# reduktor_light.net
KiCad netlist of a schematic drawn in EAGLE
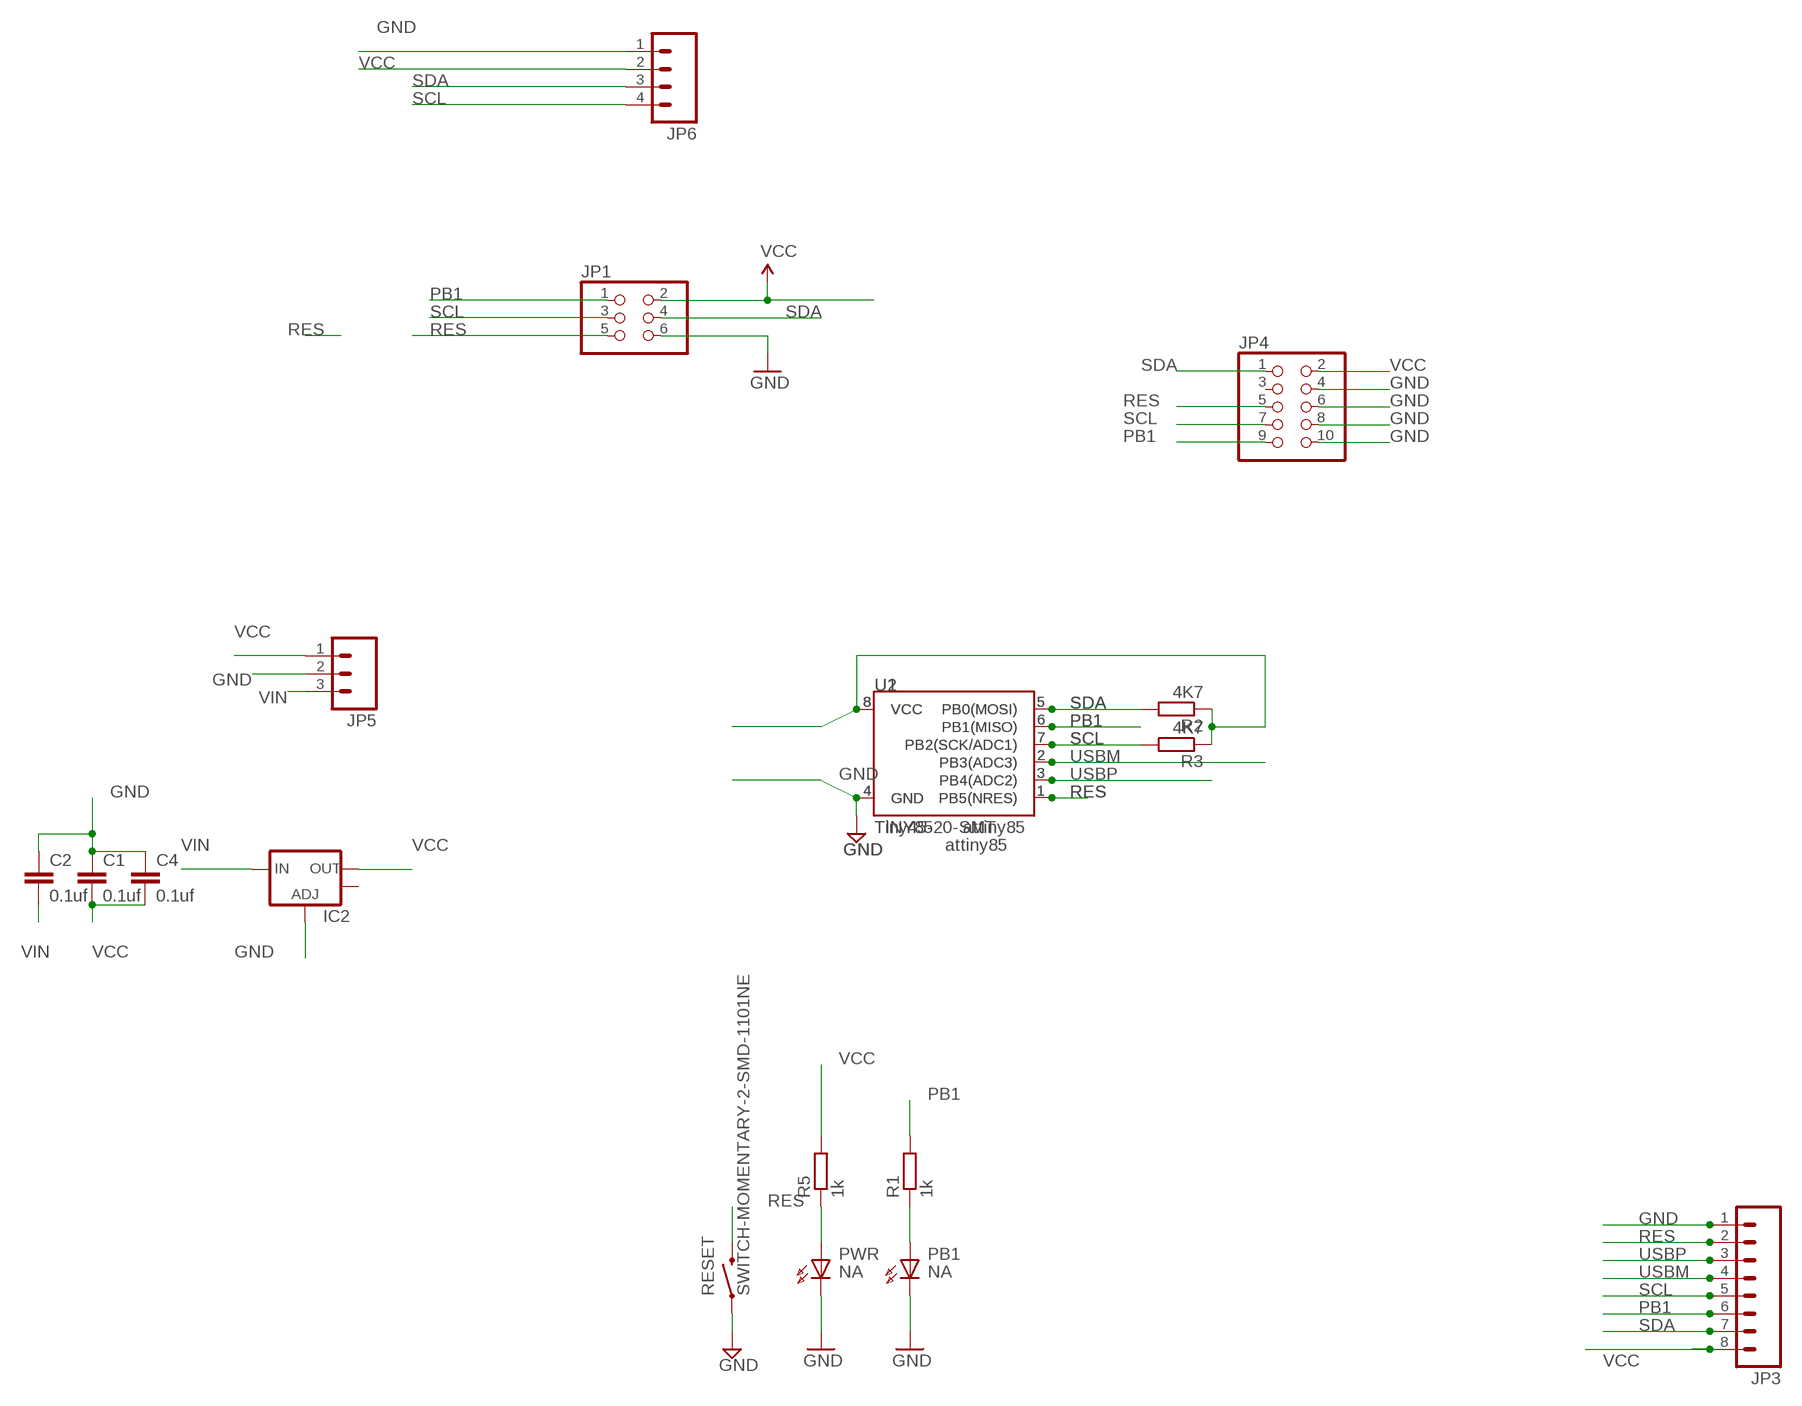
[diagram p0: schematic, sheet 1]

(export (version "E")
  (design (tool "Eeschema 10.0.6"))
  (components
    (comp (ref "C1")
      (value "0.1uf")
      (footprint "eagle-import:0603-CAP")
      (libsource (lib "eagle-import") (part "CAP0603-CAP"))
    )
    (comp (ref "C2")
      (value "0.1uf")
      (footprint "eagle-import:0603-CAP")
      (libsource (lib "eagle-import") (part "CAP0603-CAP"))
    )
    (comp (ref "C4")
      (value "0.1uf")
      (footprint "eagle-import:0603-CAP")
      (libsource (lib "eagle-import") (part "CAP0603-CAP"))
    )
    (comp (ref "IC2")
      (value "V_REG_LM1117SOT223")
      (footprint "eagle-import:SOT223")
      (libsource (lib "eagle-import") (part "V_REG_LM1117SOT223"))
    )
    (comp (ref "JP1")
      (value "PINHD-2X3")
      (footprint "eagle-import:2X03")
      (libsource (lib "eagle-import") (part "PINHD-2X3"))
    )
    (comp (ref "JP3")
      (value "M08LOCK_LONGPADS")
      (footprint "eagle-import:1X08_LOCK_LONGPADS")
      (libsource (lib "eagle-import") (part "M08LOCK_LONGPADS"))
    )
    (comp (ref "JP4")
      (value "PINHD-2X5")
      (footprint "eagle-import:2X05")
      (libsource (lib "eagle-import") (part "PINHD-2X5"))
    )
    (comp (ref "JP5")
      (value "M03LONGPADS")
      (footprint "eagle-import:1X03_LONGPADS")
      (libsource (lib "eagle-import") (part "M03LONGPADS"))
    )
    (comp (ref "JP6")
      (value "M04PTH")
      (footprint "eagle-import:1X04")
      (libsource (lib "eagle-import") (part "M04PTH"))
    )
    (comp (ref "PB1")
      (value "NA")
      (footprint "eagle-import:LED-0603")
      (libsource (lib "eagle-import") (part "LED0603DWS"))
    )
    (comp (ref "PWR")
      (value "NA")
      (footprint "eagle-import:LED-0603")
      (libsource (lib "eagle-import") (part "LED0603DWS"))
    )
    (comp (ref "R1")
      (value "1k")
      (footprint "eagle-import:R0603")
      (libsource (lib "eagle-import") (part "R-EU_R0603"))
    )
    (comp (ref "R2")
      (value "4K7")
      (footprint "eagle-import:R0603")
      (libsource (lib "eagle-import") (part "R-EU_R0603"))
    )
    (comp (ref "R3")
      (value "4K7")
      (footprint "eagle-import:R0603")
      (libsource (lib "eagle-import") (part "R-EU_R0603"))
    )
    (comp (ref "R5")
      (value "1k")
      (footprint "eagle-import:R0603")
      (libsource (lib "eagle-import") (part "R-EU_R0603"))
    )
    (comp (ref "RESET")
      (value "SWITCH-MOMENTARY-2-SMD-1101NE")
      (footprint "eagle-import:TACTILE-SWITCH-1101NE")
      (libsource (lib "eagle-import") (part "SWITCH-MOMENTARY-2-SMD-1101NE"))
    )
    (comp (ref "U1")
      (value "TINY85")
      (footprint "eagle-import:DIP08")
      (libsource (lib "eagle-import") (part "ATTINY45TINY45-20-DIP"))
    )
    (comp (ref "U2")
      (value "Tiny45-20-SMT")
      (footprint "eagle-import:SO08-EIAJ")
      (libsource (lib "eagle-import") (part "ATTINY45TINY45-20-SMT"))
    )
  )
  (nets
    (net (code "1") (name "/PB1") (class "Default")
      (node (ref "JP1") (pin "1") (pinfunction "1_1") (pintype "passive"))
      (node (ref "JP3") (pin "6") (pinfunction "6_6") (pintype "passive"))
      (node (ref "JP4") (pin "9") (pinfunction "9_9") (pintype "passive"))
      (node (ref "R1") (pin "2") (pinfunction "2_2") (pintype "passive"))
      (node (ref "U1") (pin "6") (pinfunction "PB1(MISO)_6") (pintype "bidirectional"))
      (node (ref "U2") (pin "6") (pinfunction "PB1(MISO)_6") (pintype "bidirectional"))
    )
    (net (code "2") (name "/RES") (class "Default")
      (node (ref "JP1") (pin "5") (pinfunction "5_5") (pintype "passive"))
      (node (ref "JP3") (pin "2") (pinfunction "2_2") (pintype "passive"))
      (node (ref "JP4") (pin "5") (pinfunction "5_5") (pintype "passive"))
      (node (ref "RESET") (pin "P$2") (pinfunction "2_P$2") (pintype "passive"))
      (node (ref "U1") (pin "1") (pinfunction "PB5(NRES)_1") (pintype "bidirectional"))
      (node (ref "U2") (pin "1") (pinfunction "PB5(NRES)_1") (pintype "bidirectional"))
    )
    (net (code "3") (name "/SCL") (class "Default")
      (node (ref "JP1") (pin "3") (pinfunction "3_3") (pintype "passive"))
      (node (ref "JP3") (pin "5") (pinfunction "5_5") (pintype "passive"))
      (node (ref "JP4") (pin "7") (pinfunction "7_7") (pintype "passive"))
      (node (ref "JP6") (pin "4") (pinfunction "4_4") (pintype "passive"))
      (node (ref "R3") (pin "2") (pinfunction "2_2") (pintype "passive"))
      (node (ref "U1") (pin "7") (pinfunction "PB2(SCK/ADC1)_7") (pintype "bidirectional"))
      (node (ref "U2") (pin "7") (pinfunction "PB2(SCK/ADC1)_7") (pintype "bidirectional"))
    )
    (net (code "4") (name "/SDA") (class "Default")
      (node (ref "JP1") (pin "4") (pinfunction "4_4") (pintype "passive"))
      (node (ref "JP3") (pin "7") (pinfunction "7_7") (pintype "passive"))
      (node (ref "JP4") (pin "1") (pinfunction "1_1") (pintype "passive"))
      (node (ref "JP6") (pin "3") (pinfunction "3_3") (pintype "passive"))
      (node (ref "R2") (pin "2") (pinfunction "2_2") (pintype "passive"))
      (node (ref "U1") (pin "5") (pinfunction "PB0(MOSI)_5") (pintype "bidirectional"))
      (node (ref "U2") (pin "5") (pinfunction "PB0(MOSI)_5") (pintype "bidirectional"))
    )
    (net (code "5") (name "/USBM") (class "Default")
      (node (ref "JP3") (pin "4") (pinfunction "4_4") (pintype "passive"))
      (node (ref "U1") (pin "2") (pinfunction "PB3(ADC3)_2") (pintype "bidirectional"))
      (node (ref "U2") (pin "2") (pinfunction "PB3(ADC3)_2") (pintype "bidirectional"))
    )
    (net (code "6") (name "/USBP") (class "Default")
      (node (ref "JP3") (pin "3") (pinfunction "3_3") (pintype "passive"))
      (node (ref "U1") (pin "3") (pinfunction "PB4(ADC2)_3") (pintype "bidirectional"))
      (node (ref "U2") (pin "3") (pinfunction "PB4(ADC2)_3") (pintype "bidirectional"))
    )
    (net (code "7") (name "/VIN") (class "Default")
      (node (ref "C2") (pin "2") (pinfunction "2_2") (pintype "passive"))
      (node (ref "IC2") (pin "3") (pinfunction "IN_3") (pintype "input"))
      (node (ref "JP5") (pin "3") (pinfunction "3_3") (pintype "passive"))
    )
    (net (code "8") (name "GND") (class "Default")
      (node (ref "C1") (pin "1") (pinfunction "1_1") (pintype "passive"))
      (node (ref "C2") (pin "1") (pinfunction "1_1") (pintype "passive"))
      (node (ref "C4") (pin "1") (pinfunction "1_1") (pintype "passive"))
      (node (ref "IC2") (pin "1") (pinfunction "ADJ_1") (pintype "input"))
      (node (ref "JP1") (pin "6") (pinfunction "6_6") (pintype "passive"))
      (node (ref "JP3") (pin "1") (pinfunction "1_1") (pintype "passive"))
      (node (ref "JP4") (pin "10") (pinfunction "10_10") (pintype "passive"))
      (node (ref "JP4") (pin "4") (pinfunction "4_4") (pintype "passive"))
      (node (ref "JP4") (pin "6") (pinfunction "6_6") (pintype "passive"))
      (node (ref "JP4") (pin "8") (pinfunction "8_8") (pintype "passive"))
      (node (ref "JP5") (pin "2") (pinfunction "2_2") (pintype "passive"))
      (node (ref "JP6") (pin "1") (pinfunction "1_1") (pintype "passive"))
      (node (ref "PB1") (pin "C") (pinfunction "C_C") (pintype "passive"))
      (node (ref "PWR") (pin "C") (pinfunction "C_C") (pintype "passive"))
      (node (ref "RESET") (pin "P$1") (pinfunction "1_P$1") (pintype "passive"))
      (node (ref "U1") (pin "4") (pinfunction "GND_4") (pintype "bidirectional"))
      (node (ref "U2") (pin "4") (pinfunction "GND_4") (pintype "bidirectional"))
    )
    (net (code "9") (name "Net-(PB1-PadA)") (class "Default")
      (node (ref "PB1") (pin "A") (pinfunction "A_A") (pintype "passive"))
      (node (ref "R1") (pin "1") (pinfunction "1_1") (pintype "passive"))
    )
    (net (code "10") (name "Net-(PWR-PadA)") (class "Default")
      (node (ref "PWR") (pin "A") (pinfunction "A_A") (pintype "passive"))
      (node (ref "R5") (pin "1") (pinfunction "1_1") (pintype "passive"))
    )
    (net (code "11") (name "VCC") (class "Default")
      (node (ref "C1") (pin "2") (pinfunction "2_2") (pintype "passive"))
      (node (ref "C4") (pin "2") (pinfunction "2_2") (pintype "passive"))
      (node (ref "IC2") (pin "2") (pinfunction "OUT_2") (pintype "output"))
      (node (ref "JP1") (pin "2") (pinfunction "2_2") (pintype "passive"))
      (node (ref "JP3") (pin "8") (pinfunction "8_8") (pintype "passive"))
      (node (ref "JP4") (pin "2") (pinfunction "2_2") (pintype "passive"))
      (node (ref "JP5") (pin "1") (pinfunction "1_1") (pintype "passive"))
      (node (ref "JP6") (pin "2") (pinfunction "2_2") (pintype "passive"))
      (node (ref "R2") (pin "1") (pinfunction "1_1") (pintype "passive"))
      (node (ref "R3") (pin "1") (pinfunction "1_1") (pintype "passive"))
      (node (ref "R5") (pin "2") (pinfunction "2_2") (pintype "passive"))
      (node (ref "U1") (pin "8") (pinfunction "VCC_8") (pintype "bidirectional"))
      (node (ref "U2") (pin "8") (pinfunction "VCC_8") (pintype "bidirectional"))
    )
    (net (code "12") (name "unconnected-(IC2-OUT-Pad4)") (class "Default")
      (node (ref "IC2") (pin "4") (pinfunction "OUT_4") (pintype "output"))
    )
    (net (code "13") (name "unconnected-(JP4-Pad3)") (class "Default")
      (node (ref "JP4") (pin "3") (pinfunction "3_3") (pintype "passive"))
    )
  )
)
